# cameralink.net
KiCad netlist of a schematic drawn in Altium Designer
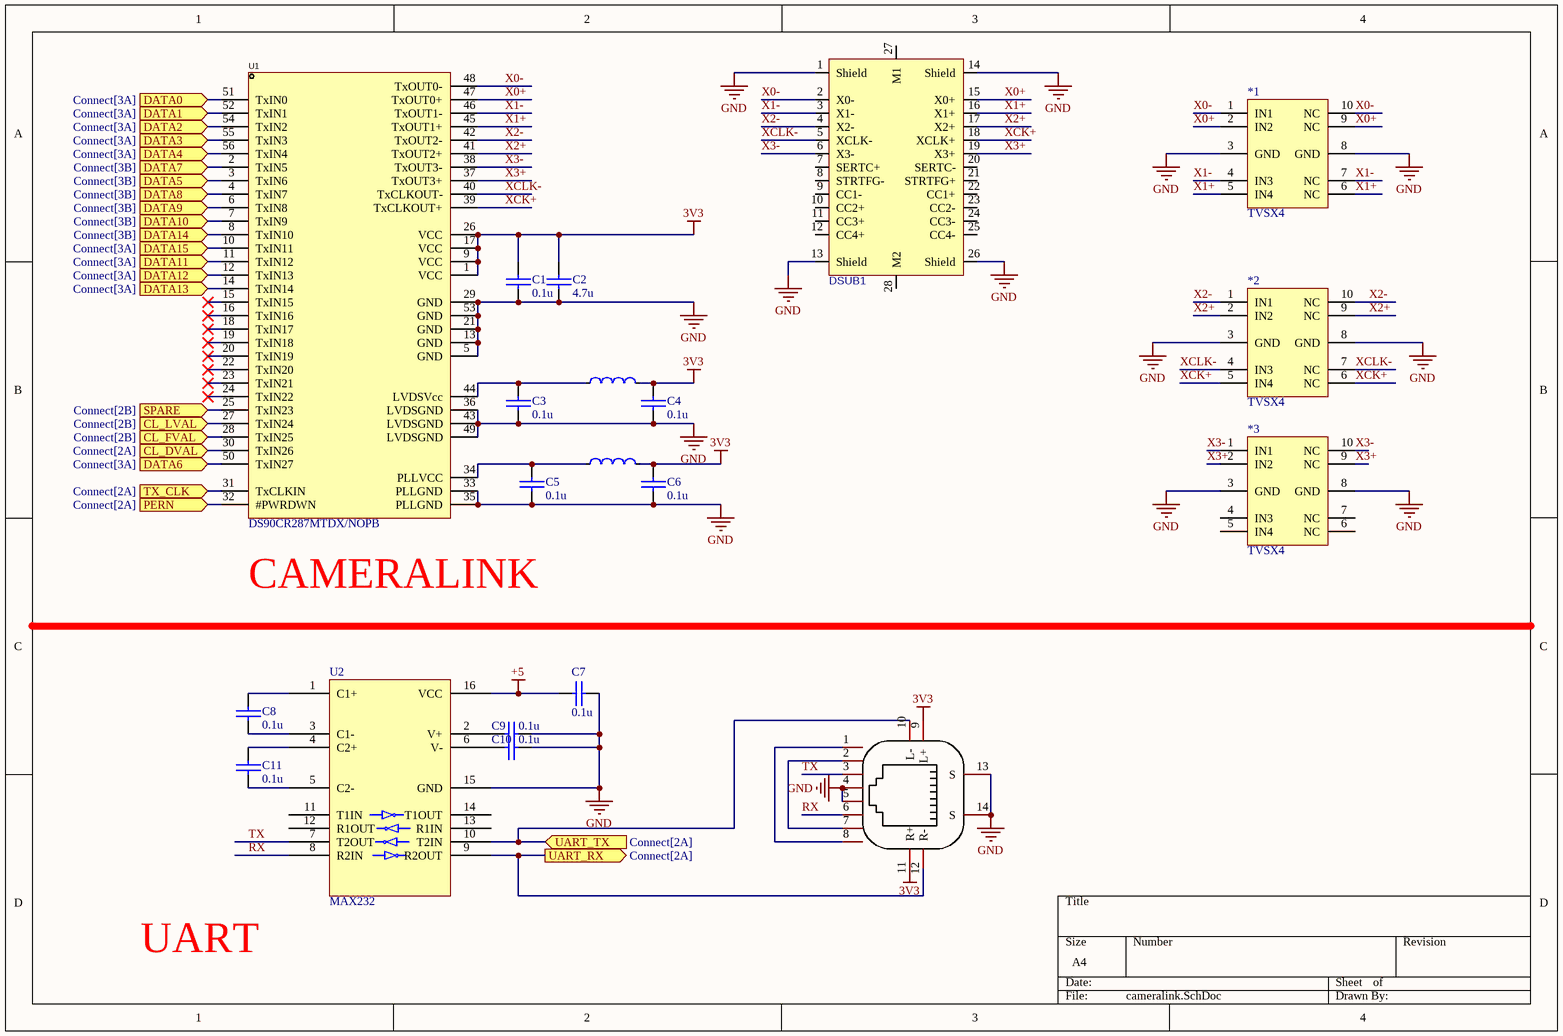
[diagram p0: cameralink.SchDoc]

(export (version "E")
  (design (tool "Eeschema 10.0.6"))
  (components
    (comp (ref "*1")
      (value "TVSX4")
      (footprint "DFN-10")
      (description "瞬态抑制二极管")
      (libsource (lib "0.05-mylib") (part "TVSX4"))
    )
    (comp (ref "*2")
      (value "TVSX4")
      (footprint "DFN-10")
      (description "瞬态抑制二极管")
      (libsource (lib "0.05-mylib") (part "TVSX4"))
    )
    (comp (ref "*3")
      (value "TVSX4")
      (footprint "DFN-10")
      (description "瞬态抑制二极管")
      (libsource (lib "0.05-mylib") (part "TVSX4"))
    )
    (comp (ref "C1")
      (value "0.1u")
      (footprint "0603C")
      (description "无极性电容")
      (libsource (lib "1.00-阻容感") (part "CAP"))
    )
    (comp (ref "C2")
      (value "4.7u")
      (footprint "0603C")
      (description "无极性电容")
      (libsource (lib "1.00-阻容感") (part "CAP"))
    )
    (comp (ref "C3")
      (value "0.1u")
      (footprint "0603C")
      (description "无极性电容")
      (libsource (lib "1.00-阻容感") (part "CAP"))
    )
    (comp (ref "C4")
      (value "0.1u")
      (footprint "0603C")
      (description "无极性电容")
      (libsource (lib "1.00-阻容感") (part "CAP"))
    )
    (comp (ref "C5")
      (value "0.1u")
      (footprint "0603C")
      (description "无极性电容")
      (libsource (lib "1.00-阻容感") (part "CAP"))
    )
    (comp (ref "C6")
      (value "0.1u")
      (footprint "0603C")
      (description "无极性电容")
      (libsource (lib "1.00-阻容感") (part "CAP"))
    )
    (comp (ref "C7")
      (value "0.1u")
      (footprint "0603C")
      (description "无极性电容")
      (libsource (lib "1.00-阻容感") (part "CAP"))
    )
    (comp (ref "C8")
      (value "0.1u")
      (footprint "0603C")
      (description "无极性电容")
      (libsource (lib "1.00-阻容感") (part "CAP"))
    )
    (comp (ref "C9")
      (value "0.1u")
      (footprint "0603C")
      (description "无极性电容")
      (libsource (lib "1.00-阻容感") (part "CAP"))
    )
    (comp (ref "C10")
      (value "0.1u")
      (footprint "0603C")
      (description "无极性电容")
      (libsource (lib "1.00-阻容感") (part "CAP"))
    )
    (comp (ref "C11")
      (value "0.1u")
      (footprint "0603C")
      (description "无极性电容")
      (libsource (lib "1.00-阻容感") (part "CAP"))
    )
    (comp (ref "DSUB1")
      (value "6321-026RDS1MWA02")
      (footprint "MDR-26-horizontal")
      (fields (field (name "BOM_SUPPLIER PART") "C843200") (field (name "CONTRIBUTOR") "LCSC"))
      (libsource (lib "0.04连接器") (part "MDR-26"))
    )
    (comp (ref "L1")
      (value "GZ1608D601TF")
      (footprint "0603L")
      (description "铁氧体磁珠")
      (fields (field (name "MANUFACTURER") "Sunlord(顺络)") (field (name "TOLERANCE") "±25%"))
      (libsource (lib "1.00-阻容感") (part "FB"))
    )
    (comp (ref "L2")
      (value "GZ1608D601TF")
      (footprint "0603L")
      (description "铁氧体磁珠")
      (fields (field (name "MANUFACTURER") "Sunlord(顺络)") (field (name "TOLERANCE") "±25%"))
      (libsource (lib "1.00-阻容感") (part "FB"))
    )
    (comp (ref "RJ1")
      (value "R-RJ45R08P-C000")
      (footprint "RJ45-TH_R-RJ45R08P-C000")
      (description "RJ45")
      (fields (field (name "MANUFACTURER") "Ckmtw(灿科盟)"))
      (libsource (lib "9.03-连接器插座") (part "RJ45R08P"))
    )
    (comp (ref "U1")
      (value "DS90CR287MTDX/NOPB")
      (footprint "TSSOP-56_L14.0-W6.1-P0.50-LS8.1-BL")
      (description "cameralink编码")
      (fields (field (name "MANUFACTURER") "TI(德州仪器)"))
      (libsource (lib "0.05-mylib") (part "DS90CR287MTDX/NOPB"))
    )
    (comp (ref "U2") (value "MAX232") (footprint "SOP16") (libsource (lib "7.06-通讯系列IC") (part "MAX232")))
  )
  (nets
    (net (code "1") (name "+5") (class "Default")
      (node (ref "C7") (pin "2") (pinfunction "2_2") (pintype "passive"))
      (node (ref "U2") (pin "16") (pinfunction "VCC_16") (pintype "passive"))
    )
    (net (code "2") (name "/CL_DVAL") (class "Default")
      (node (ref "U1") (pin "30") (pinfunction "TxIN26_30") (pintype "passive"))
    )
    (net (code "3") (name "/CL_FVAL") (class "Default")
      (node (ref "U1") (pin "28") (pinfunction "TxIN25_28") (pintype "passive"))
    )
    (net (code "4") (name "/CL_LVAL") (class "Default")
      (node (ref "U1") (pin "27") (pinfunction "TxIN24_27") (pintype "passive"))
    )
    (net (code "5") (name "/DATA0") (class "Default")
      (node (ref "U1") (pin "51") (pinfunction "TxIN0_51") (pintype "passive"))
    )
    (net (code "6") (name "/DATA1") (class "Default")
      (node (ref "U1") (pin "52") (pinfunction "TxIN1_52") (pintype "passive"))
    )
    (net (code "7") (name "/DATA2") (class "Default")
      (node (ref "U1") (pin "54") (pinfunction "TxIN2_54") (pintype "passive"))
    )
    (net (code "8") (name "/DATA3") (class "Default")
      (node (ref "U1") (pin "55") (pinfunction "TxIN3_55") (pintype "passive"))
    )
    (net (code "9") (name "/DATA4") (class "Default")
      (node (ref "U1") (pin "56") (pinfunction "TxIN4_56") (pintype "passive"))
    )
    (net (code "10") (name "/DATA5") (class "Default")
      (node (ref "U1") (pin "3") (pinfunction "TxIN6_3") (pintype "passive"))
    )
    (net (code "11") (name "/DATA6") (class "Default")
      (node (ref "U1") (pin "50") (pinfunction "TxIN27_50") (pintype "passive"))
    )
    (net (code "12") (name "/DATA7") (class "Default")
      (node (ref "U1") (pin "2") (pinfunction "TxIN5_2") (pintype "passive"))
    )
    (net (code "13") (name "/DATA8") (class "Default")
      (node (ref "U1") (pin "4") (pinfunction "TxIN7_4") (pintype "passive"))
    )
    (net (code "14") (name "/DATA9") (class "Default")
      (node (ref "U1") (pin "6") (pinfunction "TxIN8_6") (pintype "passive"))
    )
    (net (code "15") (name "/DATA10") (class "Default")
      (node (ref "U1") (pin "7") (pinfunction "TxIN9_7") (pintype "passive"))
    )
    (net (code "16") (name "/DATA11") (class "Default")
      (node (ref "U1") (pin "11") (pinfunction "TxIN12_11") (pintype "passive"))
    )
    (net (code "17") (name "/DATA12") (class "Default")
      (node (ref "U1") (pin "12") (pinfunction "TxIN13_12") (pintype "passive"))
    )
    (net (code "18") (name "/DATA13") (class "Default")
      (node (ref "U1") (pin "14") (pinfunction "TxIN14_14") (pintype "passive"))
    )
    (net (code "19") (name "/DATA14") (class "Default")
      (node (ref "U1") (pin "8") (pinfunction "TxIN10_8") (pintype "passive"))
    )
    (net (code "20") (name "/DATA15") (class "Default")
      (node (ref "U1") (pin "10") (pinfunction "TxIN11_10") (pintype "passive"))
    )
    (net (code "21") (name "/PERN") (class "Default")
      (node (ref "U1") (pin "32") (pinfunction "#PWRDWN_32") (pintype "passive"))
    )
    (net (code "22") (name "/RX") (class "Default")
      (node (ref "RJ1") (pin "6") (pinfunction "6_6") (pintype "passive"))
      (node (ref "U2") (pin "8") (pinfunction "R2IN_8") (pintype "passive"))
    )
    (net (code "23") (name "/SPARE") (class "Default")
      (node (ref "U1") (pin "25") (pinfunction "TxIN23_25") (pintype "passive"))
    )
    (net (code "24") (name "/TX") (class "Default")
      (node (ref "RJ1") (pin "3") (pinfunction "3_3") (pintype "passive"))
      (node (ref "U2") (pin "7") (pinfunction "T2OUT_7") (pintype "passive"))
    )
    (net (code "25") (name "/TX_CLK") (class "Default")
      (node (ref "U1") (pin "31") (pinfunction "TxCLKIN_31") (pintype "passive"))
    )
    (net (code "26") (name "/UART_RX") (class "Default")
      (node (ref "RJ1") (pin "12") (pinfunction "R-_12") (pintype "passive"))
      (node (ref "U2") (pin "9") (pinfunction "R2OUT_9") (pintype "passive"))
    )
    (net (code "27") (name "/UART_TX") (class "Default")
      (node (ref "RJ1") (pin "10") (pinfunction "L-_10") (pintype "passive"))
      (node (ref "U2") (pin "10") (pinfunction "T2IN_10") (pintype "passive"))
    )
    (net (code "28") (name "/X0+") (class "Default")
      (node (ref "*1") (pin "2") (pinfunction "IN2_2") (pintype "passive"))
      (node (ref "*1") (pin "9") (pinfunction "NC_9") (pintype "passive"))
      (node (ref "DSUB1") (pin "15") (pinfunction "X0+_15") (pintype "passive"))
      (node (ref "U1") (pin "47") (pinfunction "TxOUT0+_47") (pintype "passive"))
    )
    (net (code "29") (name "/X0-") (class "Default")
      (node (ref "*1") (pin "1") (pinfunction "IN1_1") (pintype "passive"))
      (node (ref "*1") (pin "10") (pinfunction "NC_10") (pintype "passive"))
      (node (ref "DSUB1") (pin "2") (pinfunction "X0-_2") (pintype "passive"))
      (node (ref "U1") (pin "48") (pinfunction "TxOUT0-_48") (pintype "passive"))
    )
    (net (code "30") (name "/X1+") (class "Default")
      (node (ref "*1") (pin "5") (pinfunction "IN4_5") (pintype "passive"))
      (node (ref "*1") (pin "6") (pinfunction "NC_6") (pintype "passive"))
      (node (ref "DSUB1") (pin "16") (pinfunction "X1+_16") (pintype "passive"))
      (node (ref "U1") (pin "45") (pinfunction "TxOUT1+_45") (pintype "passive"))
    )
    (net (code "31") (name "/X1-") (class "Default")
      (node (ref "*1") (pin "4") (pinfunction "IN3_4") (pintype "passive"))
      (node (ref "*1") (pin "7") (pinfunction "NC_7") (pintype "passive"))
      (node (ref "DSUB1") (pin "3") (pinfunction "X1-_3") (pintype "passive"))
      (node (ref "U1") (pin "46") (pinfunction "TxOUT1-_46") (pintype "passive"))
    )
    (net (code "32") (name "/X2+") (class "Default")
      (node (ref "*2") (pin "2") (pinfunction "IN2_2") (pintype "passive"))
      (node (ref "*2") (pin "9") (pinfunction "NC_9") (pintype "passive"))
      (node (ref "DSUB1") (pin "17") (pinfunction "X2+_17") (pintype "passive"))
      (node (ref "U1") (pin "41") (pinfunction "TxOUT2+_41") (pintype "passive"))
    )
    (net (code "33") (name "/X2-") (class "Default")
      (node (ref "*2") (pin "1") (pinfunction "IN1_1") (pintype "passive"))
      (node (ref "*2") (pin "10") (pinfunction "NC_10") (pintype "passive"))
      (node (ref "DSUB1") (pin "4") (pinfunction "X2-_4") (pintype "passive"))
      (node (ref "U1") (pin "42") (pinfunction "TxOUT2-_42") (pintype "passive"))
    )
    (net (code "34") (name "/X3+") (class "Default")
      (node (ref "*3") (pin "2") (pinfunction "IN2_2") (pintype "passive"))
      (node (ref "*3") (pin "9") (pinfunction "NC_9") (pintype "passive"))
      (node (ref "DSUB1") (pin "19") (pinfunction "X3+_19") (pintype "passive"))
      (node (ref "U1") (pin "37") (pinfunction "TxOUT3+_37") (pintype "passive"))
    )
    (net (code "35") (name "/X3-") (class "Default")
      (node (ref "*3") (pin "1") (pinfunction "IN1_1") (pintype "passive"))
      (node (ref "*3") (pin "10") (pinfunction "NC_10") (pintype "passive"))
      (node (ref "DSUB1") (pin "6") (pinfunction "X3-_6") (pintype "passive"))
      (node (ref "U1") (pin "38") (pinfunction "TxOUT3-_38") (pintype "passive"))
    )
    (net (code "36") (name "/XCK+") (class "Default")
      (node (ref "*2") (pin "5") (pinfunction "IN4_5") (pintype "passive"))
      (node (ref "*2") (pin "6") (pinfunction "NC_6") (pintype "passive"))
      (node (ref "DSUB1") (pin "18") (pinfunction "XCLK+_18") (pintype "passive"))
      (node (ref "U1") (pin "39") (pinfunction "TxCLKOUT+_39") (pintype "passive"))
    )
    (net (code "37") (name "/XCLK-") (class "Default")
      (node (ref "*2") (pin "4") (pinfunction "IN3_4") (pintype "passive"))
      (node (ref "*2") (pin "7") (pinfunction "NC_7") (pintype "passive"))
      (node (ref "DSUB1") (pin "5") (pinfunction "XCLK-_5") (pintype "passive"))
      (node (ref "U1") (pin "40") (pinfunction "TxCLKOUT-_40") (pintype "passive"))
    )
    (net (code "38") (name "3V3") (class "Default")
      (node (ref "C1") (pin "2") (pinfunction "2_2") (pintype "passive"))
      (node (ref "C2") (pin "2") (pinfunction "2_2") (pintype "passive"))
      (node (ref "C4") (pin "2") (pinfunction "2_2") (pintype "passive"))
      (node (ref "C6") (pin "2") (pinfunction "2_2") (pintype "passive"))
      (node (ref "L1") (pin "2") (pinfunction "2_2") (pintype "passive"))
      (node (ref "L2") (pin "2") (pinfunction "2_2") (pintype "passive"))
      (node (ref "RJ1") (pin "11") (pinfunction "R+_11") (pintype "passive"))
      (node (ref "RJ1") (pin "9") (pinfunction "L+_9") (pintype "passive"))
      (node (ref "U1") (pin "1") (pinfunction "VCC_1") (pintype "passive"))
      (node (ref "U1") (pin "17") (pinfunction "VCC_17") (pintype "passive"))
      (node (ref "U1") (pin "26") (pinfunction "VCC_26") (pintype "passive"))
      (node (ref "U1") (pin "9") (pinfunction "VCC_9") (pintype "passive"))
    )
    (net (code "39") (name "GND") (class "Default")
      (node (ref "*1") (pin "3") (pinfunction "GND_3") (pintype "passive"))
      (node (ref "*1") (pin "8") (pinfunction "GND_8") (pintype "passive"))
      (node (ref "*2") (pin "3") (pinfunction "GND_3") (pintype "passive"))
      (node (ref "*2") (pin "8") (pinfunction "GND_8") (pintype "passive"))
      (node (ref "*3") (pin "3") (pinfunction "GND_3") (pintype "passive"))
      (node (ref "*3") (pin "8") (pinfunction "GND_8") (pintype "passive"))
      (node (ref "C1") (pin "1") (pinfunction "1_1") (pintype "passive"))
      (node (ref "C10") (pin "1") (pinfunction "1_1") (pintype "passive"))
      (node (ref "C2") (pin "1") (pinfunction "1_1") (pintype "passive"))
      (node (ref "C3") (pin "1") (pinfunction "1_1") (pintype "passive"))
      (node (ref "C4") (pin "1") (pinfunction "1_1") (pintype "passive"))
      (node (ref "C5") (pin "1") (pinfunction "1_1") (pintype "passive"))
      (node (ref "C6") (pin "1") (pinfunction "1_1") (pintype "passive"))
      (node (ref "C7") (pin "1") (pinfunction "1_1") (pintype "passive"))
      (node (ref "C9") (pin "1") (pinfunction "1_1") (pintype "passive"))
      (node (ref "DSUB1") (pin "1") (pinfunction "Shield_1") (pintype "passive"))
      (node (ref "DSUB1") (pin "13") (pinfunction "Shield_13") (pintype "passive"))
      (node (ref "DSUB1") (pin "14") (pinfunction "Shield_14") (pintype "passive"))
      (node (ref "DSUB1") (pin "26") (pinfunction "Shield_26") (pintype "passive"))
      (node (ref "RJ1") (pin "13") (pinfunction "S_13") (pintype "passive"))
      (node (ref "RJ1") (pin "14") (pinfunction "S_14") (pintype "passive"))
      (node (ref "RJ1") (pin "4") (pinfunction "4_4") (pintype "passive"))
      (node (ref "RJ1") (pin "5") (pinfunction "5_5") (pintype "passive"))
      (node (ref "U1") (pin "13") (pinfunction "GND_13") (pintype "passive"))
      (node (ref "U1") (pin "21") (pinfunction "GND_21") (pintype "passive"))
      (node (ref "U1") (pin "29") (pinfunction "GND_29") (pintype "passive"))
      (node (ref "U1") (pin "33") (pinfunction "PLLGND_33") (pintype "passive"))
      (node (ref "U1") (pin "35") (pinfunction "PLLGND_35") (pintype "passive"))
      (node (ref "U1") (pin "36") (pinfunction "LVDSGND_36") (pintype "passive"))
      (node (ref "U1") (pin "43") (pinfunction "LVDSGND_43") (pintype "passive"))
      (node (ref "U1") (pin "49") (pinfunction "LVDSGND_49") (pintype "passive"))
      (node (ref "U1") (pin "5") (pinfunction "GND_5") (pintype "passive"))
      (node (ref "U1") (pin "53") (pinfunction "GND_53") (pintype "passive"))
      (node (ref "U2") (pin "15") (pinfunction "GND_15") (pintype "passive"))
    )
    (net (code "40") (name "Net-(RJ1-Pad1)") (class "Default")
      (node (ref "RJ1") (pin "1") (pinfunction "1_1") (pintype "passive"))
      (node (ref "RJ1") (pin "8") (pinfunction "8_8") (pintype "passive"))
    )
    (net (code "41") (name "Net-(RJ1-Pad2)") (class "Default")
      (node (ref "RJ1") (pin "2") (pinfunction "2_2") (pintype "passive"))
      (node (ref "RJ1") (pin "7") (pinfunction "7_7") (pintype "passive"))
    )
    (net (code "42") (name "Net-(U1-LVDSVcc)") (class "Default")
      (node (ref "C3") (pin "2") (pinfunction "2_2") (pintype "passive"))
      (node (ref "L1") (pin "1") (pinfunction "1_1") (pintype "passive"))
      (node (ref "U1") (pin "44") (pinfunction "LVDSVcc_44") (pintype "passive"))
    )
    (net (code "43") (name "Net-(U1-PLLVCC)") (class "Default")
      (node (ref "C5") (pin "2") (pinfunction "2_2") (pintype "passive"))
      (node (ref "L2") (pin "1") (pinfunction "1_1") (pintype "passive"))
      (node (ref "U1") (pin "34") (pinfunction "PLLVCC_34") (pintype "passive"))
    )
    (net (code "44") (name "Net-(U2-C1+)") (class "Default")
      (node (ref "C8") (pin "2") (pinfunction "2_2") (pintype "passive"))
      (node (ref "U2") (pin "1") (pinfunction "C1+_1") (pintype "passive"))
    )
    (net (code "45") (name "Net-(U2-C1-)") (class "Default")
      (node (ref "C8") (pin "1") (pinfunction "1_1") (pintype "passive"))
      (node (ref "U2") (pin "3") (pinfunction "C1-_3") (pintype "passive"))
    )
    (net (code "46") (name "Net-(U2-C2+)") (class "Default")
      (node (ref "C11") (pin "2") (pinfunction "2_2") (pintype "passive"))
      (node (ref "U2") (pin "4") (pinfunction "C2+_4") (pintype "passive"))
    )
    (net (code "47") (name "Net-(U2-C2-)") (class "Default")
      (node (ref "C11") (pin "1") (pinfunction "1_1") (pintype "passive"))
      (node (ref "U2") (pin "5") (pinfunction "C2-_5") (pintype "passive"))
    )
    (net (code "48") (name "Net-(U2-V+)") (class "Default")
      (node (ref "C9") (pin "2") (pinfunction "2_2") (pintype "passive"))
      (node (ref "U2") (pin "2") (pinfunction "V+_2") (pintype "passive"))
    )
    (net (code "49") (name "Net-(U2-V-)") (class "Default")
      (node (ref "C10") (pin "2") (pinfunction "2_2") (pintype "passive"))
      (node (ref "U2") (pin "6") (pinfunction "V-_6") (pintype "passive"))
    )
    (net (code "50") (name "unconnected-(*3-IN3-Pad4)") (class "Default")
      (node (ref "*3") (pin "4") (pinfunction "IN3_4") (pintype "passive"))
    )
    (net (code "51") (name "unconnected-(*3-IN4-Pad5)") (class "Default")
      (node (ref "*3") (pin "5") (pinfunction "IN4_5") (pintype "passive"))
    )
    (net (code "52") (name "unconnected-(*3-NC-Pad6)") (class "Default")
      (node (ref "*3") (pin "6") (pinfunction "NC_6") (pintype "passive"))
    )
    (net (code "53") (name "unconnected-(*3-NC-Pad7)") (class "Default")
      (node (ref "*3") (pin "7") (pinfunction "NC_7") (pintype "passive"))
    )
    (net (code "54") (name "unconnected-(DSUB1-CC1+-Pad22)") (class "Default")
      (node (ref "DSUB1") (pin "22") (pinfunction "CC1+_22") (pintype "passive"))
    )
    (net (code "55") (name "unconnected-(DSUB1-CC1--Pad9)") (class "Default")
      (node (ref "DSUB1") (pin "9") (pinfunction "CC1-_9") (pintype "passive"))
    )
    (net (code "56") (name "unconnected-(DSUB1-CC2+-Pad10)") (class "Default")
      (node (ref "DSUB1") (pin "10") (pinfunction "CC2+_10") (pintype "passive"))
    )
    (net (code "57") (name "unconnected-(DSUB1-CC2--Pad23)") (class "Default")
      (node (ref "DSUB1") (pin "23") (pinfunction "CC2-_23") (pintype "passive"))
    )
    (net (code "58") (name "unconnected-(DSUB1-CC3+-Pad11)") (class "Default")
      (node (ref "DSUB1") (pin "11") (pinfunction "CC3+_11") (pintype "passive"))
    )
    (net (code "59") (name "unconnected-(DSUB1-CC3--Pad24)") (class "Default")
      (node (ref "DSUB1") (pin "24") (pinfunction "CC3-_24") (pintype "passive"))
    )
    (net (code "60") (name "unconnected-(DSUB1-CC4+-Pad12)") (class "Default")
      (node (ref "DSUB1") (pin "12") (pinfunction "CC4+_12") (pintype "passive"))
    )
    (net (code "61") (name "unconnected-(DSUB1-CC4--Pad25)") (class "Default")
      (node (ref "DSUB1") (pin "25") (pinfunction "CC4-_25") (pintype "passive"))
    )
    (net (code "62") (name "unconnected-(DSUB1-M1-Pad27)") (class "Default")
      (node (ref "DSUB1") (pin "27") (pinfunction "M1_27") (pintype "passive"))
    )
    (net (code "63") (name "unconnected-(DSUB1-M2-Pad28)") (class "Default")
      (node (ref "DSUB1") (pin "28") (pinfunction "M2_28") (pintype "passive"))
    )
    (net (code "64") (name "unconnected-(DSUB1-SERTC+-Pad7)") (class "Default")
      (node (ref "DSUB1") (pin "7") (pinfunction "SERTC+_7") (pintype "passive"))
    )
    (net (code "65") (name "unconnected-(DSUB1-SERTC--Pad20)") (class "Default")
      (node (ref "DSUB1") (pin "20") (pinfunction "SERTC-_20") (pintype "passive"))
    )
    (net (code "66") (name "unconnected-(DSUB1-STRTFG+-Pad21)") (class "Default")
      (node (ref "DSUB1") (pin "21") (pinfunction "STRTFG+_21") (pintype "passive"))
    )
    (net (code "67") (name "unconnected-(DSUB1-STRTFG--Pad8)") (class "Default")
      (node (ref "DSUB1") (pin "8") (pinfunction "STRTFG-_8") (pintype "passive"))
    )
    (net (code "68") (name "unconnected-(U1-TxIN15-Pad15)") (class "Default")
      (node (ref "U1") (pin "15") (pinfunction "TxIN15_15") (pintype "passive+no_connect"))
    )
    (net (code "69") (name "unconnected-(U1-TxIN16-Pad16)") (class "Default")
      (node (ref "U1") (pin "16") (pinfunction "TxIN16_16") (pintype "passive+no_connect"))
    )
    (net (code "70") (name "unconnected-(U1-TxIN17-Pad18)") (class "Default")
      (node (ref "U1") (pin "18") (pinfunction "TxIN17_18") (pintype "passive+no_connect"))
    )
    (net (code "71") (name "unconnected-(U1-TxIN18-Pad19)") (class "Default")
      (node (ref "U1") (pin "19") (pinfunction "TxIN18_19") (pintype "passive+no_connect"))
    )
    (net (code "72") (name "unconnected-(U1-TxIN19-Pad20)") (class "Default")
      (node (ref "U1") (pin "20") (pinfunction "TxIN19_20") (pintype "passive+no_connect"))
    )
    (net (code "73") (name "unconnected-(U1-TxIN20-Pad22)") (class "Default")
      (node (ref "U1") (pin "22") (pinfunction "TxIN20_22") (pintype "passive+no_connect"))
    )
    (net (code "74") (name "unconnected-(U1-TxIN21-Pad23)") (class "Default")
      (node (ref "U1") (pin "23") (pinfunction "TxIN21_23") (pintype "passive+no_connect"))
    )
    (net (code "75") (name "unconnected-(U1-TxIN22-Pad24)") (class "Default")
      (node (ref "U1") (pin "24") (pinfunction "TxIN22_24") (pintype "passive+no_connect"))
    )
    (net (code "76") (name "unconnected-(U2-R1IN-Pad13)") (class "Default")
      (node (ref "U2") (pin "13") (pinfunction "R1IN_13") (pintype "passive"))
    )
    (net (code "77") (name "unconnected-(U2-R1OUT-Pad12)") (class "Default")
      (node (ref "U2") (pin "12") (pinfunction "R1OUT_12") (pintype "passive"))
    )
    (net (code "78") (name "unconnected-(U2-T1IN-Pad11)") (class "Default")
      (node (ref "U2") (pin "11") (pinfunction "T1IN_11") (pintype "passive"))
    )
    (net (code "79") (name "unconnected-(U2-T1OUT-Pad14)") (class "Default")
      (node (ref "U2") (pin "14") (pinfunction "T1OUT_14") (pintype "passive"))
    )
  )
)
